# ETHERNET.net
KiCad netlist of a schematic drawn in Altium Designer
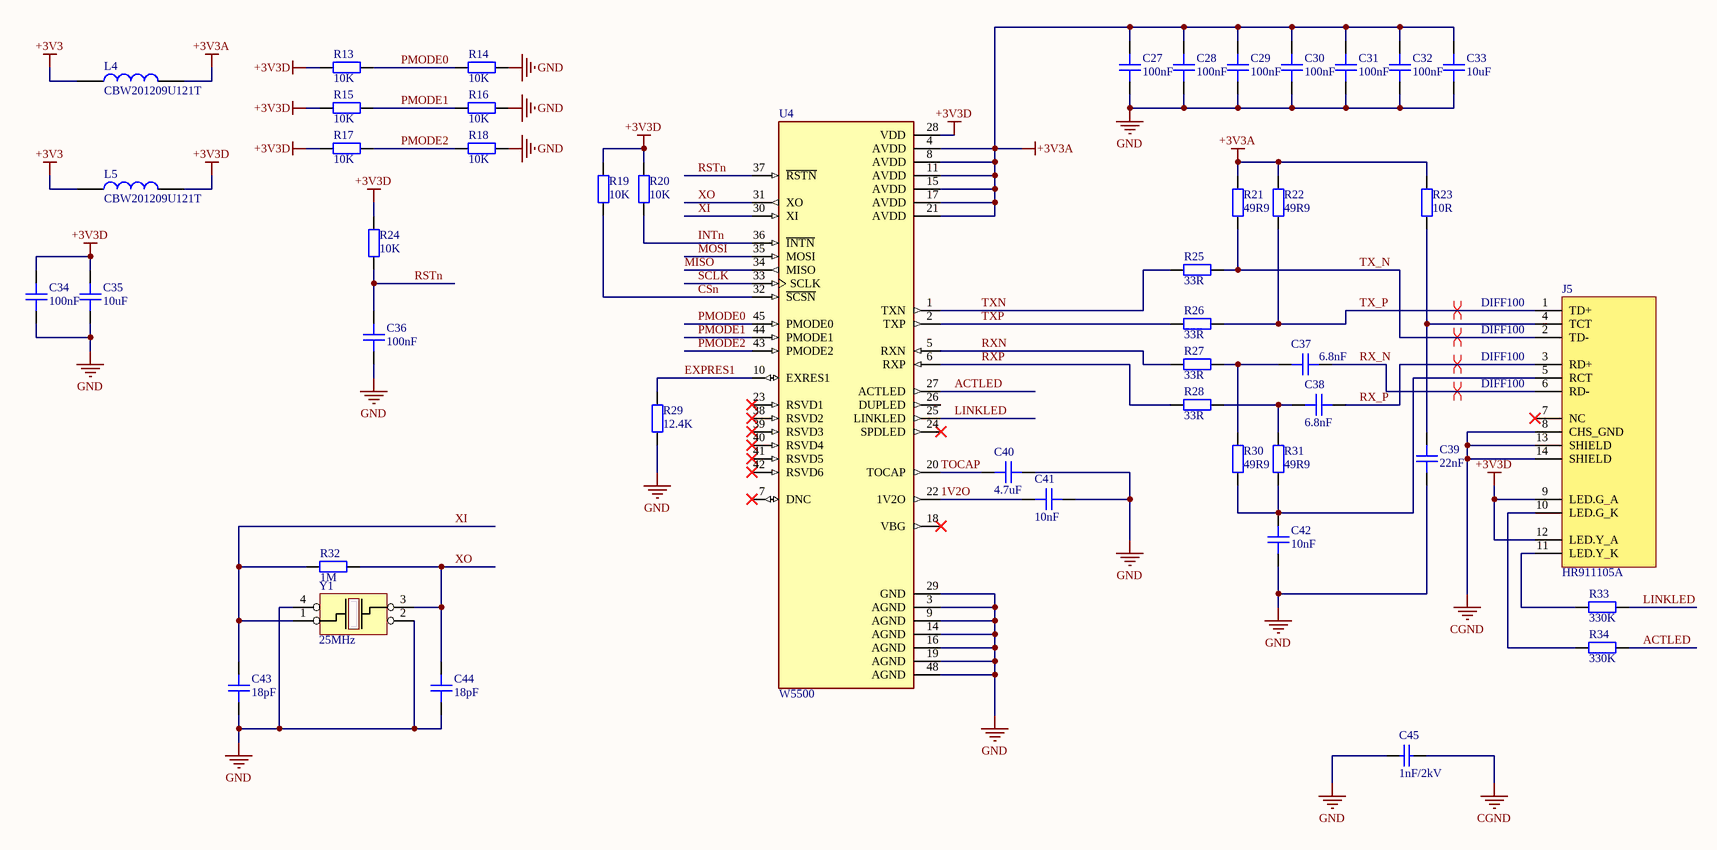
[diagram p0: ETHERNET.SchDoc]

(export (version "E")
  (design (tool "Eeschema 10.0.6"))
  (components
    (comp (ref "C27")
      (value "100nF")
      (footprint "CAPC-0603 (1608)")
      (description "CAP CER 1uF 10% 16V X7R 0603")
      (fields (field (name "MPN") "CC0603KRX7R7BB105"))
      (libsource (lib "Integrated_Library_gateway_tbl") (part "CC0603KRX7R7BB105"))
    )
    (comp (ref "C28")
      (value "100nF")
      (footprint "CAPC-0603 (1608)")
      (description "CAP CER 1uF 10% 16V X7R 0603")
      (fields (field (name "MPN") "CC0603KRX7R7BB105"))
      (libsource (lib "Integrated_Library_gateway_tbl") (part "CC0603KRX7R7BB105"))
    )
    (comp (ref "C29")
      (value "100nF")
      (footprint "CAPC-0603 (1608)")
      (description "CAP CER 1uF 10% 16V X7R 0603")
      (fields (field (name "MPN") "CC0603KRX7R7BB105"))
      (libsource (lib "Integrated_Library_gateway_tbl") (part "CC0603KRX7R7BB105"))
    )
    (comp (ref "C30")
      (value "100nF")
      (footprint "CAPC-0603 (1608)")
      (description "CAP CER 1uF 10% 16V X7R 0603")
      (fields (field (name "MPN") "CC0603KRX7R7BB105"))
      (libsource (lib "Integrated_Library_gateway_tbl") (part "CC0603KRX7R7BB105"))
    )
    (comp (ref "C31")
      (value "100nF")
      (footprint "CAPC-0603 (1608)")
      (description "CAP CER 1uF 10% 16V X7R 0603")
      (fields (field (name "MPN") "CC0603KRX7R7BB105"))
      (libsource (lib "Integrated_Library_gateway_tbl") (part "CC0603KRX7R7BB105"))
    )
    (comp (ref "C32")
      (value "100nF")
      (footprint "CAPC-0603 (1608)")
      (description "CAP CER 1uF 10% 16V X7R 0603")
      (fields (field (name "MPN") "CC0603KRX7R7BB105"))
      (libsource (lib "Integrated_Library_gateway_tbl") (part "CC0603KRX7R7BB105"))
    )
    (comp (ref "C33")
      (value "10uF")
      (footprint "CAPC-0603 (1608)")
      (description "CAP CER 0.018UF 50V X7R 0603")
      (fields (field (name "MPN") "CC0603JRX7R9BB183") (field (name "MFR") "Yageo"))
      (libsource (lib "Integrated_Library_gateway_tbl") (part "CC0603JRX7R9BB183"))
    )
    (comp (ref "C34")
      (value "100nF")
      (footprint "CAPC-0603 (1608)")
      (description "CAP CER 1uF 10% 16V X7R 0603")
      (fields (field (name "MPN") "CC0603KRX7R7BB105"))
      (libsource (lib "Integrated_Library_gateway_tbl") (part "CC0603KRX7R7BB105"))
    )
    (comp (ref "C35")
      (value "10uF")
      (footprint "CAPC-0603 (1608)")
      (description "CAP CER 0.018UF 50V X7R 0603")
      (fields (field (name "MPN") "CC0603JRX7R9BB183") (field (name "MFR") "Yageo"))
      (libsource (lib "Integrated_Library_gateway_tbl") (part "CC0603JRX7R9BB183"))
    )
    (comp (ref "C36")
      (value "100nF")
      (footprint "CAPC-0603 (1608)")
      (description "CAP CER 1uF 10% 16V X7R 0603")
      (fields (field (name "MPN") "CC0603KRX7R7BB105"))
      (libsource (lib "Integrated_Library_gateway_tbl") (part "CC0603KRX7R7BB105"))
    )
    (comp (ref "C37")
      (value "6.8nF")
      (footprint "CAPC-0603 (1608)")
      (description "CAP CER 6.8nF 5% 50V X7R 0603")
      (fields (field (name "MPN") "CC0603JRX7R9BB682"))
      (libsource (lib "Integrated_Library_gateway_tbl") (part "CC0603JRX7R9BB682"))
    )
    (comp (ref "C38")
      (value "6.8nF")
      (footprint "CAPC-0603 (1608)")
      (description "CAP CER 6.8nF 5% 50V X7R 0603")
      (fields (field (name "MPN") "CC0603JRX7R9BB682"))
      (libsource (lib "Integrated_Library_gateway_tbl") (part "CC0603JRX7R9BB682"))
    )
    (comp (ref "C39")
      (value "22nF")
      (footprint "CAPC-0603 (1608)")
      (description "CAP CER 0.22UF 16V X7R 0603")
      (fields (field (name "MPN") "CC0603KRX7R7BB224") (field (name "MFR") "Yageo"))
      (libsource (lib "Integrated_Library_gateway_tbl") (part "CC0603KRX7R7BB224"))
    )
    (comp (ref "C40")
      (value "4.7uF")
      (footprint "CAPC-0603 (1608)")
      (description "CAP CER 470pF 50V 5% C0G/NPO 0603")
      (fields (field (name "MPN") "CC0603JRNPO9BN471"))
      (libsource (lib "Integrated_Library_gateway_tbl") (part "CC0603JRNPO9BN471"))
    )
    (comp (ref "C41")
      (value "10nF")
      (footprint "CAPC-0603 (1608)")
      (description "CAP CER 10nF 16V 10% X7R 0603")
      (fields (field (name "MPN") "CC0603KRX7R7BB103"))
      (libsource (lib "Integrated_Library_gateway_tbl") (part "CC0603KRX7R7BB103"))
    )
    (comp (ref "C42")
      (value "10nF")
      (footprint "CAPC-0603 (1608)")
      (description "CAP CER 10nF 16V 10% X7R 0603")
      (fields (field (name "MPN") "CC0603KRX7R7BB103"))
      (libsource (lib "Integrated_Library_gateway_tbl") (part "CC0603KRX7R7BB103"))
    )
    (comp (ref "C43")
      (value "18pF")
      (footprint "CAPC-0603 (1608)")
      (description "CAP CER 180PF 50V 5% COG/NPO 0603")
      (fields (field (name "MPN") "CC0603JRNPO9BN181"))
      (libsource (lib "Integrated_Library_gateway_tbl") (part "CC0603JRNPO9BN181"))
    )
    (comp (ref "C44")
      (value "18pF")
      (footprint "CAPC-0603 (1608)")
      (description "CAP CER 180PF 50V 5% COG/NPO 0603")
      (fields (field (name "MPN") "CC0603JRNPO9BN181"))
      (libsource (lib "Integrated_Library_gateway_tbl") (part "CC0603JRNPO9BN181"))
    )
    (comp (ref "C45")
      (value "1nF/2kV")
      (footprint "tu 1206")
      (description "Dán")
      (libsource (lib "Integrated_Library_gateway_tbl") (part "Tu 1206 470pF 50V 10%"))
    )
    (comp (ref "J5")
      (value "HR911105A")
      (footprint "HR911105A")
      (description "Hanrun HR911105A RJ-45 Connector")
      (fields (field (name "MFR") "HanRun"))
      (libsource (lib "Integrated_Library_gateway_tbl") (part "HR911105A"))
    )
    (comp (ref "L4")
      (value "CBW201209U121T")
      (footprint "IND-0805 (2012)")
      (description "IND-FERRITE BEAD 220 OHM 0805 1LN")
      (fields (field (name "MPN") "MPZ2012S221A"))
      (libsource (lib "Integrated_Library_gateway_tbl") (part "MPZ2012S221A"))
    )
    (comp (ref "L5")
      (value "CBW201209U121T")
      (footprint "IND-0805 (2012)")
      (description "IND-FERRITE BEAD 220 OHM 0805 1LN")
      (fields (field (name "MPN") "MPZ2012S221A"))
      (libsource (lib "") (part "MPZ2012S221A_1"))
    )
    (comp (ref "R13")
      (value "10K")
      (footprint "RESC-0603 (1608)")
      (description "RES SMD 10K OHM 1% 1/10W 0603")
      (fields (field (name "MPN") "RC0603FR-0710KL"))
      (libsource (lib "") (part "RC0603FR-0710KL_1"))
    )
    (comp (ref "R14")
      (value "10K")
      (footprint "RESC-0603 (1608)")
      (description "RES SMD 10K OHM 1% 1/10W 0603")
      (fields (field (name "MPN") "RC0603FR-0710KL"))
      (libsource (lib "") (part "RC0603FR-0710KL_1"))
    )
    (comp (ref "R15")
      (value "10K")
      (footprint "RESC-0603 (1608)")
      (description "RES SMD 10K OHM 1% 1/10W 0603")
      (fields (field (name "MPN") "RC0603FR-0710KL"))
      (libsource (lib "") (part "RC0603FR-0710KL_1"))
    )
    (comp (ref "R16")
      (value "10K")
      (footprint "RESC-0603 (1608)")
      (description "RES SMD 10K OHM 1% 1/10W 0603")
      (fields (field (name "MPN") "RC0603FR-0710KL"))
      (libsource (lib "") (part "RC0603FR-0710KL_1"))
    )
    (comp (ref "R17")
      (value "10K")
      (footprint "RESC-0603 (1608)")
      (description "RES SMD 10K OHM 1% 1/10W 0603")
      (fields (field (name "MPN") "RC0603FR-0710KL"))
      (libsource (lib "") (part "RC0603FR-0710KL_1"))
    )
    (comp (ref "R18")
      (value "10K")
      (footprint "RESC-0603 (1608)")
      (description "RES SMD 10K OHM 1% 1/10W 0603")
      (fields (field (name "MPN") "RC0603FR-0710KL"))
      (libsource (lib "") (part "RC0603FR-0710KL_1"))
    )
    (comp (ref "R19")
      (value "10K")
      (footprint "RESC-0603 (1608)")
      (description "RES SMD 10K OHM 1% 1/10W 0603")
      (fields (field (name "MPN") "RC0603FR-0710KL"))
      (libsource (lib "Integrated_Library_gateway_tbl") (part "RC0603FR-0710KL"))
    )
    (comp (ref "R20")
      (value "10K")
      (footprint "RESC-0603 (1608)")
      (description "RES SMD 10K OHM 1% 1/10W 0603")
      (fields (field (name "MPN") "RC0603FR-0710KL"))
      (libsource (lib "Integrated_Library_gateway_tbl") (part "RC0603FR-0710KL"))
    )
    (comp (ref "R21")
      (value "49R9")
      (footprint "RESC-0603 (1608)")
      (description "RES SMD 49.9 OHM 1% 1/10W 0603")
      (fields (field (name "MPN") "RC0603FR-0749R9L") (field (name "MFR") "Yageo"))
      (libsource (lib "Integrated_Library_gateway_tbl") (part "RC0603FR-0749R9L"))
    )
    (comp (ref "R22")
      (value "49R9")
      (footprint "RESC-0603 (1608)")
      (description "RES SMD 49.9 OHM 1% 1/10W 0603")
      (fields (field (name "MPN") "RC0603FR-0749R9L") (field (name "MFR") "Yageo"))
      (libsource (lib "Integrated_Library_gateway_tbl") (part "RC0603FR-0749R9L"))
    )
    (comp (ref "R23")
      (value "10R")
      (footprint "RESC-0603 (1608)")
      (description "RES SMD 10 OHM 1% 1/10W 0603")
      (fields (field (name "MPN") "RC0603FR-0710RL"))
      (libsource (lib "Integrated_Library_gateway_tbl") (part "RC0603FR-0710RL"))
    )
    (comp (ref "R24")
      (value "10K")
      (footprint "RESC-0603 (1608)")
      (description "RES SMD 10K OHM 1% 1/10W 0603")
      (fields (field (name "MPN") "RC0603FR-0710KL"))
      (libsource (lib "Integrated_Library_gateway_tbl") (part "RC0603FR-0710KL"))
    )
    (comp (ref "R25")
      (value "33R")
      (footprint "RESC-0603 (1608)")
      (description "RES SMD 33 OHM 1% 1/10W 0603")
      (fields (field (name "MPN") "RC0603FR-0733RL") (field (name "MFR") "Yageo"))
      (libsource (lib "Integrated_Library_gateway_tbl") (part "RC0603FR-0733RL"))
    )
    (comp (ref "R26")
      (value "33R")
      (footprint "RESC-0603 (1608)")
      (description "RES SMD 33 OHM 1% 1/10W 0603")
      (fields (field (name "MPN") "RC0603FR-0733RL") (field (name "MFR") "Yageo"))
      (libsource (lib "Integrated_Library_gateway_tbl") (part "RC0603FR-0733RL"))
    )
    (comp (ref "R27")
      (value "33R")
      (footprint "RESC-0603 (1608)")
      (description "RES SMD 33 OHM 1% 1/10W 0603")
      (fields (field (name "MPN") "RC0603FR-0733RL") (field (name "MFR") "Yageo"))
      (libsource (lib "Integrated_Library_gateway_tbl") (part "RC0603FR-0733RL"))
    )
    (comp (ref "R28")
      (value "33R")
      (footprint "RESC-0603 (1608)")
      (description "RES SMD 33 OHM 1% 1/10W 0603")
      (fields (field (name "MPN") "RC0603FR-0733RL") (field (name "MFR") "Yageo"))
      (libsource (lib "Integrated_Library_gateway_tbl") (part "RC0603FR-0733RL"))
    )
    (comp (ref "R29")
      (value "12.4K")
      (footprint "RESC-0603 (1608)")
      (description "RES SMD 12KOHM 1% 1/10W 0603")
      (fields (field (name "MPN") "RC0603FR-0712KL"))
      (libsource (lib "Integrated_Library_gateway_tbl") (part "RC0603FR-0712KL"))
    )
    (comp (ref "R30")
      (value "49R9")
      (footprint "RESC-0603 (1608)")
      (description "RES SMD 49.9 OHM 1% 1/10W 0603")
      (fields (field (name "MPN") "RC0603FR-0749R9L") (field (name "MFR") "Yageo"))
      (libsource (lib "Integrated_Library_gateway_tbl") (part "RC0603FR-0749R9L"))
    )
    (comp (ref "R31")
      (value "49R9")
      (footprint "RESC-0603 (1608)")
      (description "RES SMD 49.9 OHM 1% 1/10W 0603")
      (fields (field (name "MPN") "RC0603FR-0749R9L") (field (name "MFR") "Yageo"))
      (libsource (lib "Integrated_Library_gateway_tbl") (part "RC0603FR-0749R9L"))
    )
    (comp (ref "R32")
      (value "1M")
      (footprint "RESC-0603 (1608)")
      (description "RES SMD 10M OHM 1% 1/10W 0603")
      (fields (field (name "MPN") "RC0603FR-0710ML"))
      (libsource (lib "Integrated_Library_gateway_tbl") (part "RC0603FR-0710ML"))
    )
    (comp (ref "R33")
      (value "330K")
      (footprint "RESC-0603 (1608)")
      (description "RES SMD 330K OHM 1% 1/10W 0603")
      (fields (field (name "MPN") "RC0603FR-07330KL"))
      (libsource (lib "Integrated_Library_gateway_tbl") (part "RC0603FR-07330KL"))
    )
    (comp (ref "R34")
      (value "330K")
      (footprint "RESC-0603 (1608)")
      (description "RES SMD 330K OHM 1% 1/10W 0603")
      (fields (field (name "MPN") "RC0603FR-07330KL"))
      (libsource (lib "Integrated_Library_gateway_tbl") (part "RC0603FR-07330KL"))
    )
    (comp (ref "U4")
      (value "W5500")
      (footprint "QFP50P900X900X160-48N")
      (description "Hardwired TCP/IP embedded Ethernet controller")
      (libsource (lib "Integrated_Library_gateway_tbl") (part "W5500"))
    )
    (comp (ref "Y1")
      (value "25MHz")
      (footprint "CRYSTALL_SMD_3225")
      (description "CRYSTAL 25.0000MHZ 18PF SMD")
      (fields (field (name "MPN") "ABM8G-25.000MHZ-18-D2Y-T") (field (name "MFR") "Abracon LLC"))
      (libsource (lib "Integrated_Library_gateway_tbl") (part "ABM8G-25.000MHZ-18-D2Y-T"))
    )
  )
  (nets
    (net (code "1") (name "+3V3") (class "Default")
      (node (ref "L4") (pin "2") (pinfunction "2_2") (pintype "passive"))
      (node (ref "L5") (pin "1") (pinfunction "1_1") (pintype "passive"))
    )
    (net (code "2") (name "+3V3A") (class "Default")
      (node (ref "C27") (pin "2") (pinfunction "2_2") (pintype "passive"))
      (node (ref "C28") (pin "2") (pinfunction "2_2") (pintype "passive"))
      (node (ref "C29") (pin "2") (pinfunction "2_2") (pintype "passive"))
      (node (ref "C30") (pin "2") (pinfunction "2_2") (pintype "passive"))
      (node (ref "C31") (pin "2") (pinfunction "2_2") (pintype "passive"))
      (node (ref "C32") (pin "2") (pinfunction "2_2") (pintype "passive"))
      (node (ref "C33") (pin "2") (pinfunction "2_2") (pintype "passive"))
      (node (ref "L4") (pin "1") (pinfunction "1_1") (pintype "passive"))
      (node (ref "R21") (pin "2") (pinfunction "2_2") (pintype "passive"))
      (node (ref "R22") (pin "2") (pinfunction "2_2") (pintype "passive"))
      (node (ref "R23") (pin "2") (pinfunction "2_2") (pintype "passive"))
      (node (ref "U4") (pin "11") (pinfunction "AVDD_11") (pintype "power_in"))
      (node (ref "U4") (pin "15") (pinfunction "AVDD_15") (pintype "power_in"))
      (node (ref "U4") (pin "17") (pinfunction "AVDD_17") (pintype "power_in"))
      (node (ref "U4") (pin "21") (pinfunction "AVDD_21") (pintype "power_in"))
      (node (ref "U4") (pin "4") (pinfunction "AVDD_4") (pintype "power_in"))
      (node (ref "U4") (pin "8") (pinfunction "AVDD_8") (pintype "power_in"))
    )
    (net (code "3") (name "+3V3D") (class "Default")
      (node (ref "C34") (pin "2") (pinfunction "2_2") (pintype "passive"))
      (node (ref "C35") (pin "2") (pinfunction "2_2") (pintype "passive"))
      (node (ref "J5") (pin "12") (pinfunction "LED.Y_A_12") (pintype "passive"))
      (node (ref "J5") (pin "9") (pinfunction "LED.G_A_9") (pintype "passive"))
      (node (ref "L5") (pin "2") (pinfunction "2_2") (pintype "passive"))
      (node (ref "R13") (pin "1") (pinfunction "1_1") (pintype "passive"))
      (node (ref "R15") (pin "1") (pinfunction "1_1") (pintype "passive"))
      (node (ref "R17") (pin "1") (pinfunction "1_1") (pintype "passive"))
      (node (ref "R19") (pin "2") (pinfunction "2_2") (pintype "passive"))
      (node (ref "R20") (pin "2") (pinfunction "2_2") (pintype "passive"))
      (node (ref "R24") (pin "2") (pinfunction "2_2") (pintype "passive"))
      (node (ref "U4") (pin "28") (pinfunction "VDD_28") (pintype "power_in"))
    )
    (net (code "4") (name "/1V2O") (class "Default")
      (node (ref "C41") (pin "1") (pinfunction "1_1") (pintype "passive"))
      (node (ref "U4") (pin "22") (pinfunction "1V2O_22") (pintype "output"))
    )
    (net (code "5") (name "/ACTLED") (class "Default")
      (node (ref "R34") (pin "2") (pinfunction "2_2") (pintype "passive"))
      (node (ref "U4") (pin "27") (pinfunction "ACTLED_27") (pintype "output"))
    )
    (net (code "6") (name "/CSn") (class "Default")
      (node (ref "R19") (pin "1") (pinfunction "1_1") (pintype "passive"))
      (node (ref "U4") (pin "32") (pinfunction "~{SCSN}_32") (pintype "input"))
    )
    (net (code "7") (name "/EXPRES1") (class "Default")
      (node (ref "R29") (pin "2") (pinfunction "2_2") (pintype "passive"))
      (node (ref "U4") (pin "10") (pinfunction "EXRES1_10") (pintype "bidirectional"))
    )
    (net (code "8") (name "/INTn") (class "Default")
      (node (ref "R20") (pin "1") (pinfunction "1_1") (pintype "passive"))
      (node (ref "U4") (pin "36") (pinfunction "~{INTN}_36") (pintype "input"))
    )
    (net (code "9") (name "/LINKLED") (class "Default")
      (node (ref "R33") (pin "2") (pinfunction "2_2") (pintype "passive"))
      (node (ref "U4") (pin "25") (pinfunction "LINKLED_25") (pintype "output"))
    )
    (net (code "10") (name "/MISO") (class "Default")
      (node (ref "U4") (pin "34") (pinfunction "MISO_34") (pintype "output"))
    )
    (net (code "11") (name "/MOSI") (class "Default")
      (node (ref "U4") (pin "35") (pinfunction "MOSI_35") (pintype "input"))
    )
    (net (code "12") (name "/PMODE0") (class "Default")
      (node (ref "R13") (pin "2") (pinfunction "2_2") (pintype "passive"))
      (node (ref "R14") (pin "1") (pinfunction "1_1") (pintype "passive"))
      (node (ref "U4") (pin "45") (pinfunction "PMODE0_45") (pintype "input"))
    )
    (net (code "13") (name "/PMODE1") (class "Default")
      (node (ref "R15") (pin "2") (pinfunction "2_2") (pintype "passive"))
      (node (ref "R16") (pin "1") (pinfunction "1_1") (pintype "passive"))
      (node (ref "U4") (pin "44") (pinfunction "PMODE1_44") (pintype "input"))
    )
    (net (code "14") (name "/PMODE2") (class "Default")
      (node (ref "R17") (pin "2") (pinfunction "2_2") (pintype "passive"))
      (node (ref "R18") (pin "1") (pinfunction "1_1") (pintype "passive"))
      (node (ref "U4") (pin "43") (pinfunction "PMODE2_43") (pintype "input"))
    )
    (net (code "15") (name "/RSTn") (class "Default")
      (node (ref "C36") (pin "2") (pinfunction "2_2") (pintype "passive"))
      (node (ref "R24") (pin "1") (pinfunction "1_1") (pintype "passive"))
      (node (ref "U4") (pin "37") (pinfunction "~{RSTN}_37") (pintype "input"))
    )
    (net (code "16") (name "/RXN") (class "Default")
      (node (ref "R27") (pin "1") (pinfunction "1_1") (pintype "passive"))
      (node (ref "U4") (pin "5") (pinfunction "RXN_5") (pintype "input"))
    )
    (net (code "17") (name "/RXP") (class "Default")
      (node (ref "R28") (pin "1") (pinfunction "1_1") (pintype "passive"))
      (node (ref "U4") (pin "6") (pinfunction "RXP_6") (pintype "input"))
    )
    (net (code "18") (name "/RX_N") (class "Default")
      (node (ref "C37") (pin "2") (pinfunction "2_2") (pintype "passive"))
      (node (ref "J5") (pin "6") (pinfunction "RD-_6") (pintype "passive"))
    )
    (net (code "19") (name "/RX_P") (class "Default")
      (node (ref "C38") (pin "2") (pinfunction "2_2") (pintype "passive"))
      (node (ref "J5") (pin "3") (pinfunction "RD+_3") (pintype "passive"))
    )
    (net (code "20") (name "/SCLK") (class "Default")
      (node (ref "U4") (pin "33") (pinfunction "SCLK_33") (pintype "input"))
    )
    (net (code "21") (name "/TOCAP") (class "Default")
      (node (ref "C40") (pin "1") (pinfunction "1_1") (pintype "passive"))
      (node (ref "U4") (pin "20") (pinfunction "TOCAP_20") (pintype "output"))
    )
    (net (code "22") (name "/TXN") (class "Default")
      (node (ref "R25") (pin "1") (pinfunction "1_1") (pintype "passive"))
      (node (ref "U4") (pin "1") (pinfunction "TXN_1") (pintype "output"))
    )
    (net (code "23") (name "/TXP") (class "Default")
      (node (ref "R26") (pin "1") (pinfunction "1_1") (pintype "passive"))
      (node (ref "U4") (pin "2") (pinfunction "TXP_2") (pintype "output"))
    )
    (net (code "24") (name "/TX_N") (class "Default")
      (node (ref "J5") (pin "2") (pinfunction "TD-_2") (pintype "passive"))
      (node (ref "R21") (pin "1") (pinfunction "1_1") (pintype "passive"))
      (node (ref "R25") (pin "2") (pinfunction "2_2") (pintype "passive"))
    )
    (net (code "25") (name "/TX_P") (class "Default")
      (node (ref "J5") (pin "1") (pinfunction "TD+_1") (pintype "passive"))
      (node (ref "R22") (pin "1") (pinfunction "1_1") (pintype "passive"))
      (node (ref "R26") (pin "2") (pinfunction "2_2") (pintype "passive"))
    )
    (net (code "26") (name "/XI") (class "Default")
      (node (ref "C43") (pin "2") (pinfunction "2_2") (pintype "passive"))
      (node (ref "R32") (pin "1") (pinfunction "1_1") (pintype "passive"))
      (node (ref "U4") (pin "30") (pinfunction "XI_30") (pintype "input"))
      (node (ref "Y1") (pin "1") (pinfunction "1_1") (pintype "passive"))
    )
    (net (code "27") (name "/XO") (class "Default")
      (node (ref "C44") (pin "2") (pinfunction "2_2") (pintype "passive"))
      (node (ref "R32") (pin "2") (pinfunction "2_2") (pintype "passive"))
      (node (ref "U4") (pin "31") (pinfunction "XO_31") (pintype "output"))
      (node (ref "Y1") (pin "3") (pinfunction "3_3") (pintype "passive"))
    )
    (net (code "28") (name "CGND") (class "Default")
      (node (ref "C45") (pin "1") (pinfunction "1_1") (pintype "passive"))
      (node (ref "J5") (pin "13") (pinfunction "SHIELD_13") (pintype "passive"))
      (node (ref "J5") (pin "14") (pinfunction "SHIELD_14") (pintype "passive"))
      (node (ref "J5") (pin "8") (pinfunction "CHS_GND_8") (pintype "passive"))
    )
    (net (code "29") (name "GND") (class "Default")
      (node (ref "C27") (pin "1") (pinfunction "1_1") (pintype "passive"))
      (node (ref "C28") (pin "1") (pinfunction "1_1") (pintype "passive"))
      (node (ref "C29") (pin "1") (pinfunction "1_1") (pintype "passive"))
      (node (ref "C30") (pin "1") (pinfunction "1_1") (pintype "passive"))
      (node (ref "C31") (pin "1") (pinfunction "1_1") (pintype "passive"))
      (node (ref "C32") (pin "1") (pinfunction "1_1") (pintype "passive"))
      (node (ref "C33") (pin "1") (pinfunction "1_1") (pintype "passive"))
      (node (ref "C34") (pin "1") (pinfunction "1_1") (pintype "passive"))
      (node (ref "C35") (pin "1") (pinfunction "1_1") (pintype "passive"))
      (node (ref "C36") (pin "1") (pinfunction "1_1") (pintype "passive"))
      (node (ref "C39") (pin "1") (pinfunction "1_1") (pintype "passive"))
      (node (ref "C40") (pin "2") (pinfunction "2_2") (pintype "passive"))
      (node (ref "C41") (pin "2") (pinfunction "2_2") (pintype "passive"))
      (node (ref "C42") (pin "1") (pinfunction "1_1") (pintype "passive"))
      (node (ref "C43") (pin "1") (pinfunction "1_1") (pintype "passive"))
      (node (ref "C44") (pin "1") (pinfunction "1_1") (pintype "passive"))
      (node (ref "C45") (pin "2") (pinfunction "2_2") (pintype "passive"))
      (node (ref "R14") (pin "2") (pinfunction "2_2") (pintype "passive"))
      (node (ref "R16") (pin "2") (pinfunction "2_2") (pintype "passive"))
      (node (ref "R18") (pin "2") (pinfunction "2_2") (pintype "passive"))
      (node (ref "R29") (pin "1") (pinfunction "1_1") (pintype "passive"))
      (node (ref "U4") (pin "14") (pinfunction "AGND_14") (pintype "power_in"))
      (node (ref "U4") (pin "16") (pinfunction "AGND_16") (pintype "power_in"))
      (node (ref "U4") (pin "19") (pinfunction "AGND_19") (pintype "power_in"))
      (node (ref "U4") (pin "29") (pinfunction "GND_29") (pintype "passive"))
      (node (ref "U4") (pin "3") (pinfunction "AGND_3") (pintype "power_in"))
      (node (ref "U4") (pin "48") (pinfunction "AGND_48") (pintype "power_in"))
      (node (ref "U4") (pin "9") (pinfunction "AGND_9") (pintype "power_in"))
      (node (ref "Y1") (pin "2") (pinfunction "2_2") (pintype "passive"))
      (node (ref "Y1") (pin "4") (pinfunction "4_4") (pintype "passive"))
    )
    (net (code "30") (name "Net-(C37-Pad1)") (class "Default")
      (node (ref "C37") (pin "1") (pinfunction "1_1") (pintype "passive"))
      (node (ref "R27") (pin "2") (pinfunction "2_2") (pintype "passive"))
      (node (ref "R30") (pin "2") (pinfunction "2_2") (pintype "passive"))
    )
    (net (code "31") (name "Net-(C38-Pad1)") (class "Default")
      (node (ref "C38") (pin "1") (pinfunction "1_1") (pintype "passive"))
      (node (ref "R28") (pin "2") (pinfunction "2_2") (pintype "passive"))
      (node (ref "R31") (pin "2") (pinfunction "2_2") (pintype "passive"))
    )
    (net (code "32") (name "Net-(J5-LED.G_K)") (class "Default")
      (node (ref "J5") (pin "10") (pinfunction "LED.G_K_10") (pintype "passive"))
      (node (ref "R34") (pin "1") (pinfunction "1_1") (pintype "passive"))
    )
    (net (code "33") (name "Net-(J5-LED.Y_K)") (class "Default")
      (node (ref "J5") (pin "11") (pinfunction "LED.Y_K_11") (pintype "passive"))
      (node (ref "R33") (pin "1") (pinfunction "1_1") (pintype "passive"))
    )
    (net (code "34") (name "Net-(J5-RCT)") (class "Default")
      (node (ref "C42") (pin "2") (pinfunction "2_2") (pintype "passive"))
      (node (ref "J5") (pin "5") (pinfunction "RCT_5") (pintype "passive"))
      (node (ref "R30") (pin "1") (pinfunction "1_1") (pintype "passive"))
      (node (ref "R31") (pin "1") (pinfunction "1_1") (pintype "passive"))
    )
    (net (code "35") (name "Net-(J5-TCT)") (class "Default")
      (node (ref "C39") (pin "2") (pinfunction "2_2") (pintype "passive"))
      (node (ref "J5") (pin "4") (pinfunction "TCT_4") (pintype "passive"))
      (node (ref "R23") (pin "1") (pinfunction "1_1") (pintype "passive"))
    )
    (net (code "36") (name "unconnected-(J5-NC-Pad7)") (class "Default")
      (node (ref "J5") (pin "7") (pinfunction "NC_7") (pintype "passive+no_connect"))
    )
    (net (code "37") (name "unconnected-(U4-DNC-Pad7)") (class "Default")
      (node (ref "U4") (pin "7") (pinfunction "DNC_7") (pintype "bidirectional+no_connect"))
    )
    (net (code "38") (name "unconnected-(U4-DUPLED-Pad26)") (class "Default")
      (node (ref "U4") (pin "26") (pinfunction "DUPLED_26") (pintype "output"))
    )
    (net (code "39") (name "unconnected-(U4-RSVD1-Pad23)") (class "Default")
      (node (ref "U4") (pin "23") (pinfunction "RSVD1_23") (pintype "input+no_connect"))
    )
    (net (code "40") (name "unconnected-(U4-RSVD2-Pad38)") (class "Default")
      (node (ref "U4") (pin "38") (pinfunction "RSVD2_38") (pintype "input+no_connect"))
    )
    (net (code "41") (name "unconnected-(U4-RSVD3-Pad39)") (class "Default")
      (node (ref "U4") (pin "39") (pinfunction "RSVD3_39") (pintype "input+no_connect"))
    )
    (net (code "42") (name "unconnected-(U4-RSVD4-Pad40)") (class "Default")
      (node (ref "U4") (pin "40") (pinfunction "RSVD4_40") (pintype "input+no_connect"))
    )
    (net (code "43") (name "unconnected-(U4-RSVD5-Pad41)") (class "Default")
      (node (ref "U4") (pin "41") (pinfunction "RSVD5_41") (pintype "input+no_connect"))
    )
    (net (code "44") (name "unconnected-(U4-RSVD6-Pad42)") (class "Default")
      (node (ref "U4") (pin "42") (pinfunction "RSVD6_42") (pintype "input+no_connect"))
    )
    (net (code "45") (name "unconnected-(U4-SPDLED-Pad24)") (class "Default")
      (node (ref "U4") (pin "24") (pinfunction "SPDLED_24") (pintype "output+no_connect"))
    )
    (net (code "46") (name "unconnected-(U4-VBG-Pad18)") (class "Default")
      (node (ref "U4") (pin "18") (pinfunction "VBG_18") (pintype "output+no_connect"))
    )
  )
)
